# PWR.net
KiCad netlist of a schematic drawn in Altium Designer
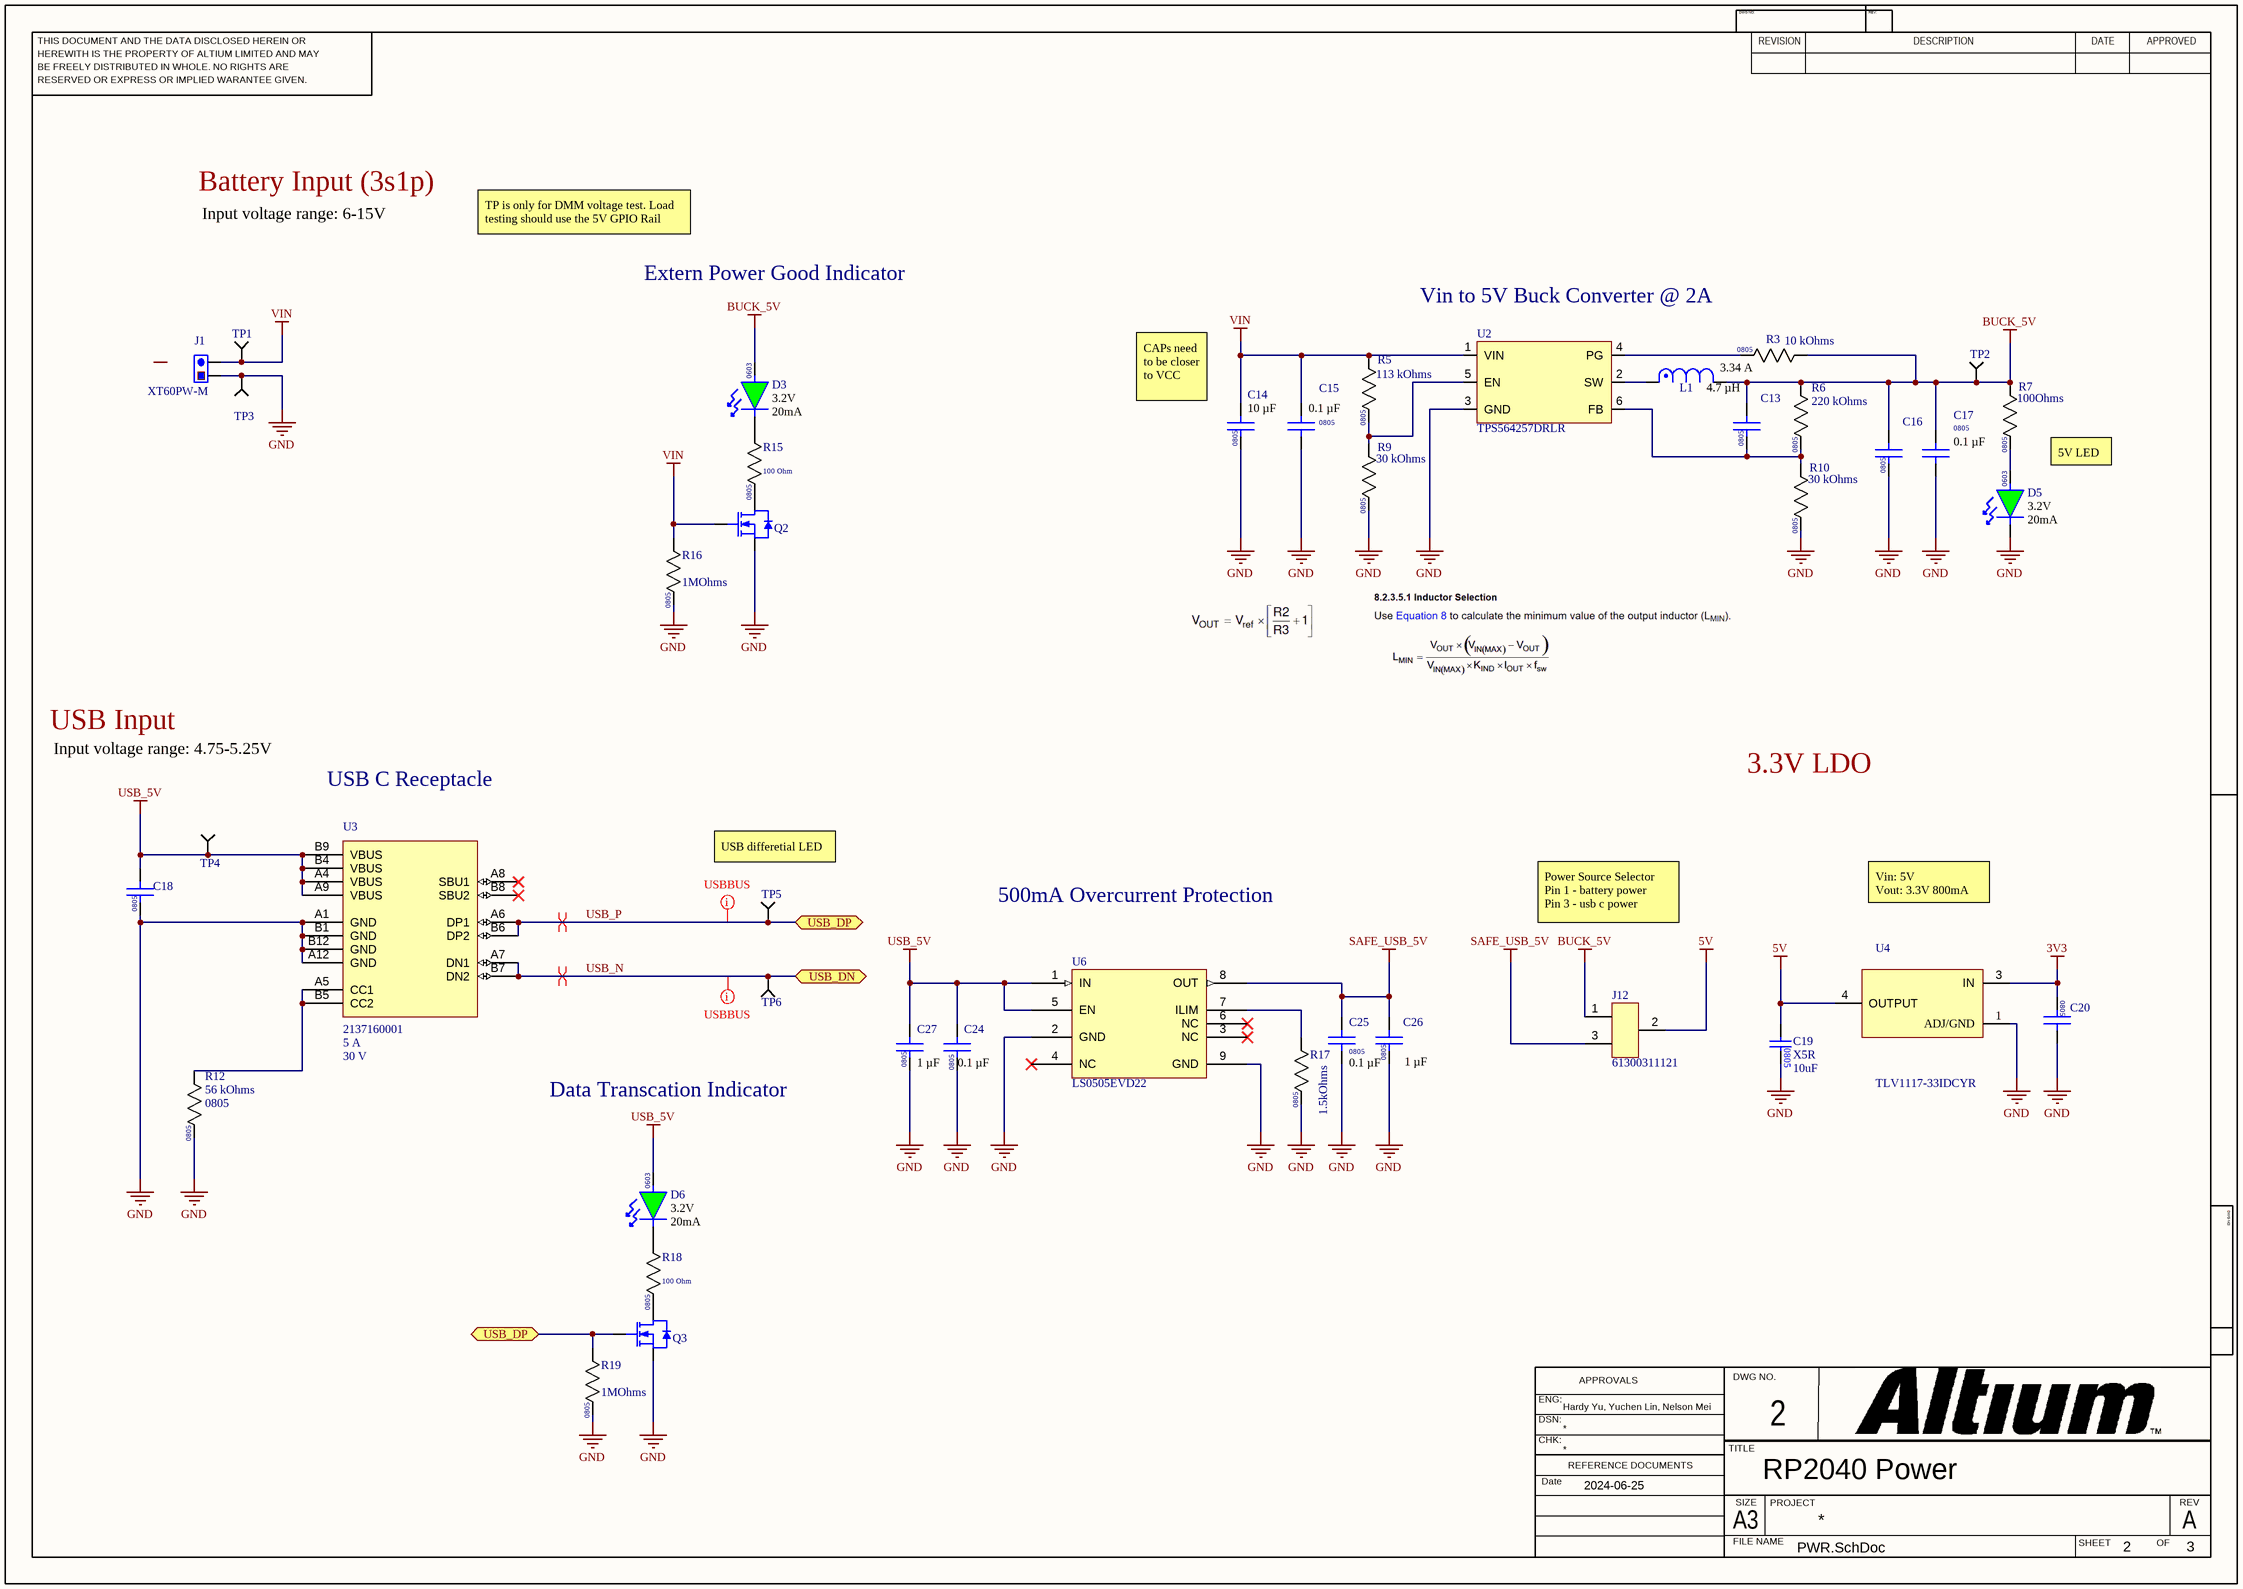
[diagram p0: PWR.SchDoc]

(export (version "E")
  (design (tool "Eeschema 10.0.6"))
  (components
    (comp (ref "C13")
      (value "C0805C300J4HAC7800")
      (footprint "CAP_CL21_SAM")
      (description "30 pF ±5% 16V Ceramic Capacitor X8R 0805 (2012 Metric)")
      (libsource (lib "RP2040_dev_board") (part "C0805C300J4HAC7800"))
    )
    (comp (ref "C14")
      (value "CL21A106KOQNNNE")
      (footprint "CAP_CL21_SAM")
      (description "10 µF ±10% 16V Ceramic Capacitor X5R 0805 (2012 Metric)")
      (fields (field (name "CAPACITANCE") "10 µF"))
      (libsource (lib "RP2040_dev_board") (part "CL21A106KOQNNNE"))
    )
    (comp (ref "C15")
      (value "C0805C104K4RAC7800")
      (footprint "CAP_CL21_SAM")
      (description "0.1 µF ±10% 16V Ceramic Capacitor X7R 0805 (2012 Metric)")
      (fields (field (name "CAPACITANCE") "0.1 µF") (field (name "PACKAGE / CASE") "0805"))
      (libsource (lib "RP2040_dev_board") (part "C0805C104K4RAC7800"))
    )
    (comp (ref "C16")
      (value "CL21A226MOCLRNC")
      (footprint "CAP_CL21_SAM")
      (description "22 µF ±20% 16V Ceramic Capacitor X5R 0805 (2012 Metric)")
      (libsource (lib "RP2040_dev_board") (part "CL21A226MOCLRNC"))
    )
    (comp (ref "C17")
      (value "C0805C104K4RAC7800")
      (footprint "CAP_CL21_SAM")
      (description "0.1 µF ±10% 16V Ceramic Capacitor X7R 0805 (2012 Metric)")
      (fields (field (name "CAPACITANCE") "0.1 µF") (field (name "PACKAGE / CASE") "0805"))
      (libsource (lib "RP2040_dev_board") (part "C0805C104K4RAC7800"))
    )
    (comp (ref "C18")
      (value "CC0805MRX7R9BB103")
      (footprint "CAP_CL21_SAM")
      (description "10000 pF ±20% 50V Ceramic Capacitor X7R 0805 (2012 Metric)")
      (fields (field (name "VOLTAGE") "50V") (field (name "TOLERANCE") "20%"))
      (libsource (lib "RP2040_dev_board") (part "CC0805MRX7R9BB103"))
    )
    (comp (ref "C19")
      (value "10uF")
      (footprint ".CAP_0805-Footprint-1")
      (description "CAP CER 10UF 16V X5R 0805")
      (fields
        (field (name "VOLTAGE") "16V")
        (field (name "TEMPERATURE COEFFICIENT") "X5R")
        (field (name "Comment") "CL21A106KOQNNNE")
      )
      (libsource (lib "WARG") (part ".CAP_0805-Symbol-1"))
    )
    (comp (ref "C20")
      (value "EMK325ABJ107MM-T")
      (footprint "CAP_EMK325AB_3P2X2P5_TAY-L")
      (description "100 µF ±20% 16V Ceramic Capacitor X5R 1210 (3225 Metric)")
      (fields (field (name "TOLERANCE") "20%"))
      (libsource (lib "RP2040_dev_board") (part "EMK325ABJ107MM-T"))
    )
    (comp (ref "C24")
      (value "C0805C104K4RAC7800")
      (footprint "CAP_CL21_SAM")
      (description "0.1 µF ±10% 16V Ceramic Capacitor X7R 0805 (2012 Metric)")
      (fields (field (name "CAPACITANCE") "0.1 µF") (field (name "PACKAGE / CASE") "0805"))
      (libsource (lib "RP2040_dev_board") (part "C0805C104K4RAC7800"))
    )
    (comp (ref "C25")
      (value "C0805C104K4RAC7800")
      (footprint "CAP_CL21_SAM")
      (description "0.1 µF ±10% 16V Ceramic Capacitor X7R 0805 (2012 Metric)")
      (fields (field (name "CAPACITANCE") "0.1 µF") (field (name "PACKAGE / CASE") "0805"))
      (libsource (lib "RP2040_dev_board") (part "C0805C104K4RAC7800"))
    )
    (comp (ref "C26")
      (value "0805B105K250DC")
      (footprint "CAP_CL21_SAM")
      (description "CAP SMD,0805,X7R,1UF,10%,25V")
      (fields (field (name "CAPACITANCE") "1 µF"))
      (libsource (lib "RP2040_dev_board") (part "0805B105K250DC"))
    )
    (comp (ref "C27")
      (value "0805B105K250DC")
      (footprint "CAP_CL21_SAM")
      (description "CAP SMD,0805,X7R,1UF,10%,25V")
      (fields (field (name "CAPACITANCE") "1 µF"))
      (libsource (lib "RP2040_dev_board") (part "0805B105K250DC"))
    )
    (comp (ref "D3")
      (value "150060GS75000")
      (footprint ".LED_0603-Footprint-1")
      (description "Green 520nm LED Indication - Discrete 3.2V 0603 (1608 Metric)")
      (fields (field (name "VOLTAGE - FORWARD (VF) (TYP)") "3.2V") (field (name "CURRENT - TEST") "20mA"))
      (libsource (lib "RP2040_dev_board") (part "150060GS75000"))
    )
    (comp (ref "D5")
      (value "150060GS75000")
      (footprint ".LED_0603-Footprint-1")
      (description "Green 520nm LED Indication - Discrete 3.2V 0603 (1608 Metric)")
      (fields (field (name "VOLTAGE - FORWARD (VF) (TYP)") "3.2V") (field (name "CURRENT - TEST") "20mA"))
      (libsource (lib "RP2040_dev_board") (part "150060GS75000"))
    )
    (comp (ref "D6")
      (value "150060GS75000")
      (footprint ".LED_0603-Footprint-1")
      (description "Green 520nm LED Indication - Discrete 3.2V 0603 (1608 Metric)")
      (fields (field (name "VOLTAGE - FORWARD (VF) (TYP)") "3.2V") (field (name "CURRENT - TEST") "20mA"))
      (libsource (lib "RP2040_dev_board") (part "150060GS75000"))
    )
    (comp (ref "J1")
      (value "XT60PW-M")
      (footprint "AMASS_XT60PW-M")
      (description "Socket, DC supply, male, PIN: 2")
      (fields (field (name "MF") "AMASS"))
      (libsource (lib "RP2040_dev_board") (part "XT60PW-M"))
    )
    (comp (ref "J12")
      (value "61300311121")
      (footprint "61300311121")
      (description "CONN HEADER VERT 3POS 2.54MM")
      (libsource (lib "RP2040_dev_board") (part "61300311121"))
    )
    (comp (ref "L1")
      (value "DR74-4R7-R")
      (footprint "DR74")
      (description "4.7 µH Shielded Drum Core, Wirewound Inductor 3.34 A 25.4mOhm Nonstandard")
      (fields (field (name "REFDES") "4.7 µH") (field (name "CURRENT RATING (AMPS)") "3.34 A"))
      (libsource (lib "RP2040_dev_board") (part "DR74-4R7-R"))
    )
    (comp (ref "Q2")
      (value "DMG2302UKQ-7")
      (footprint ".SOT23-3")
      (description "MOSFET N-CH 20V 2.8A SOT23 T&R 3")
      (libsource (lib "WARG") (part ".NCH"))
    )
    (comp (ref "Q3")
      (value "DMG2302UKQ-7")
      (footprint ".SOT23-3")
      (description "MOSFET N-CH 20V 2.8A SOT23 T&R 3")
      (libsource (lib "WARG") (part ".NCH"))
    )
    (comp (ref "R3")
      (value "ERJ-6GEYJ103V")
      (footprint "RESC1608X50N")
      (description "10 kOhms ±5% 0.125W, 1/8W Chip Resistor 0805 (2012 Metric) Automotive AEC-Q200 Thick Film")
      (fields (field (name "RESISTANCE") "10 kOhms") (field (name "TOLERANCE") "±5%"))
      (libsource (lib "RP2040_dev_board") (part "ERJ-6GEYJ103V"))
    )
    (comp (ref "R5")
      (value "ERJ-6ENF1133V")
      (footprint "RESC1608X50N")
      (description "113 kOhms ±1% 0.125W, 1/8W Chip Resistor 0805 (2012 Metric) Automotive AEC-Q200 Thick Film")
      (fields (field (name "RESISTANCE") "113 kOhms") (field (name "TOLERANCE") "±1%"))
      (libsource (lib "RP2040_dev_board") (part "ERJ-6ENF1133V"))
    )
    (comp (ref "R6")
      (value "CRG0805F220K")
      (footprint "RESC2012X65N")
      (description "220 kOhms ±1% 0.125W, 1/8W Chip Resistor 0805 (2012 Metric) Thick Film")
      (fields (field (name "RESISTANCE") "220 kOhms") (field (name "TOLERANCE") "±1%"))
      (libsource (lib "RP2040_dev_board") (part "CRG0805F220K"))
    )
    (comp (ref "R7")
      (value "RC0603FR-07100RL")
      (footprint "RESC2012X65N")
      (description "100 Ohms ±1% 0.1W, 1/10W Chip Resistor 0603 (1608 Metric) Moisture Resistant Thick Film")
      (fields (field (name "RESISTANCE") "100Ohms") (field (name "TOLERANCE") "±1%"))
      (libsource (lib "RP2040_dev_board") (part "RC0603FR-07100RL"))
    )
    (comp (ref "R9")
      (value "RMCF0805FT30K0")
      (footprint "RESC2012X65N")
      (description "30 kOhms ±1% 0.125W, 1/8W Chip Resistor 0805 (2012 Metric) Automotive AEC-Q200 Thick Film")
      (fields (field (name "RESISTANCE") "30 kOhms") (field (name "TOLERANCE") "±1%"))
      (libsource (lib "RP2040_dev_board") (part "RMCF0805FT30K0"))
    )
    (comp (ref "R10")
      (value "RMCF0805FT30K0")
      (footprint "RESC2012X65N")
      (description "30 kOhms ±1% 0.125W, 1/8W Chip Resistor 0805 (2012 Metric) Automotive AEC-Q200 Thick Film")
      (fields (field (name "RESISTANCE") "30 kOhms") (field (name "TOLERANCE") "±1%"))
      (libsource (lib "RP2040_dev_board") (part "RMCF0805FT30K0"))
    )
    (comp (ref "R12")
      (value "ERJ-6GEYJ563V")
      (footprint "RES_ERJ-6GEYJ563V")
      (description "56 kOhms ±5% 0.125W, 1/8W Chip Resistor 0805 (2012 Metric) Automotive AEC-Q200 Thick Film")
      (fields
        (field (name "RESISTANCE") "56 kOhms")
        (field (name "TOLERANCE") "±5%")
        (field (name "PACKAGE") "0805")
      )
      (libsource (lib "RP2040_dev_board") (part "ERJ-6GEYJ563V"))
    )
    (comp (ref "R15")
      (value "RMCF0805FT100R")
      (footprint ".RES_0805-Footprint-1")
      (description "RES 100 OHM 1% 1/8W 0805")
      (fields (field (name "RESISTENCE") "100 Ohm"))
      (libsource (lib "RP2040_dev_board") (part "RMCF0805FT100R"))
    )
    (comp (ref "R16")
      (value "RC0805FR-071ML")
      (footprint ".RES_0805-Footprint-1")
      (description "RES 1M OHM 1% 1/8W 0805")
      (fields (field (name "POWER") "1/8W") (field (name "RESISTANCE") "1MOhms"))
      (libsource (lib "RP2040_dev_board") (part "RC0805FR-071ML"))
    )
    (comp (ref "R17")
      (value "RC0805FR-071K5L")
      (footprint "RESC2012X65N")
      (description "1.5 kOhms ±1% 0.125W, 1/8W Chip Resistor 0805 (2012 Metric) Moisture Resistant Thick Film")
      (fields (field (name "RESISTANCE") "1.5kOhms") (field (name "TOLERANCE") "±1%"))
      (libsource (lib "RP2040_dev_board") (part "RC0805FR-071K5L"))
    )
    (comp (ref "R18")
      (value "RMCF0805FT100R")
      (footprint ".RES_0805-Footprint-1")
      (description "RES 100 OHM 1% 1/8W 0805")
      (fields (field (name "RESISTENCE") "100 Ohm"))
      (libsource (lib "RP2040_dev_board") (part "RMCF0805FT100R"))
    )
    (comp (ref "R19")
      (value "RC0805FR-071ML")
      (footprint ".RES_0805-Footprint-1")
      (description "RES 1M OHM 1% 1/8W 0805")
      (fields (field (name "POWER") "1/8W") (field (name "RESISTANCE") "1MOhms"))
      (libsource (lib "RP2040_dev_board") (part "RC0805FR-071ML"))
    )
    (comp (ref "TP1")
      (value "5002")
      (footprint "KEYSTONE_5002")
      (fields (field (name "MF") "Keystone Electronics"))
      (libsource (lib "RP2040_dev_board") (part "5002"))
    )
    (comp (ref "TP2")
      (value "5002")
      (footprint "KEYSTONE_5002")
      (fields (field (name "MF") "Keystone Electronics"))
      (libsource (lib "RP2040_dev_board") (part "5002"))
    )
    (comp (ref "TP3")
      (value "5002")
      (footprint "KEYSTONE_5002")
      (fields (field (name "MF") "Keystone Electronics"))
      (libsource (lib "RP2040_dev_board") (part "5002"))
    )
    (comp (ref "TP4")
      (value "5002")
      (footprint "KEYSTONE_5002")
      (fields (field (name "MF") "Keystone Electronics"))
      (libsource (lib "RP2040_dev_board") (part "5002"))
    )
    (comp (ref "TP5")
      (value "5002")
      (footprint "KEYSTONE_5002")
      (fields (field (name "MF") "Keystone Electronics"))
      (libsource (lib "RP2040_dev_board") (part "5002"))
    )
    (comp (ref "TP6")
      (value "5002")
      (footprint "KEYSTONE_5002")
      (fields (field (name "MF") "Keystone Electronics"))
      (libsource (lib "RP2040_dev_board") (part "5002"))
    )
    (comp (ref "U2")
      (value "TPS564257DRLR")
      (footprint "TPS564242DRLR_TEX")
      (description "Buck Switching Regulator IC Positive Adjustable 0.6V 1 Output 4A SOT-563, SOT-666")
      (libsource (lib "RP2040_dev_board") (part "TPS564257DRLR"))
    )
    (comp (ref "U3")
      (value "2137160001")
      (footprint "MOLEX_2137160001")
      (description "CONN RCPT USB2.0 TYPE C 24POS RA")
      (fields (field (name "RATED CURENT") "5 A") (field (name "RATED VOLTAGE") "30 V"))
      (libsource (lib "RP2040_dev_board") (part "2137160001"))
    )
    (comp (ref "U4")
      (value "TLV1117-33IDCYR")
      (footprint "DCY0004A_L")
      (description "800-mA, 15-V, linear voltage regulator, 3.3V fixoutput, Adjustable output")
      (libsource (lib "RP2040_dev_board") (part "TLV1117-33IDCYR"))
    )
    (comp (ref "U6")
      (value "LS0505EVD22")
      (footprint "LS0505EVD22_LTF")
      (description "IC ELECTRONIC FUSE 10DFN")
      (libsource (lib "RP2040_dev_board") (part "LS0505EVD22"))
    )
  )
  (nets
    (net (code "1") (name "/USB_N") (class "Default")
      (node (ref "TP6") (pin "TP") (pinfunction "TP_TP") (pintype "passive"))
      (node (ref "U3") (pin "A7") (pinfunction "DN1_A7") (pintype "bidirectional"))
      (node (ref "U3") (pin "B7") (pinfunction "DN2_B7") (pintype "bidirectional"))
    )
    (net (code "2") (name "/USB_P") (class "Default")
      (node (ref "Q3") (pin "1") (pinfunction "Gate_1") (pintype "passive"))
      (node (ref "R19") (pin "1") (pinfunction "1_1") (pintype "passive"))
      (node (ref "TP5") (pin "TP") (pinfunction "TP_TP") (pintype "passive"))
      (node (ref "U3") (pin "A6") (pinfunction "DP1_A6") (pintype "bidirectional"))
      (node (ref "U3") (pin "B6") (pinfunction "DP2_B6") (pintype "bidirectional"))
    )
    (net (code "3") (name "3V3") (class "Default")
      (node (ref "C20") (pin "1") (pinfunction "1_1") (pintype "passive"))
      (node (ref "U4") (pin "3") (pinfunction "IN_3") (pintype "power_in"))
    )
    (net (code "4") (name "5V") (class "Default")
      (node (ref "C19") (pin "1") (pinfunction "1_1") (pintype "passive"))
      (node (ref "J12") (pin "2") (pinfunction "2_2") (pintype "passive"))
      (node (ref "U4") (pin "4") (pinfunction "OUTPUT_4") (pintype "power_in"))
    )
    (net (code "5") (name "BUCK_5V") (class "Default")
      (node (ref "C13") (pin "2") (pinfunction "2_2") (pintype "passive"))
      (node (ref "C16") (pin "2") (pinfunction "2_2") (pintype "passive"))
      (node (ref "C17") (pin "2") (pinfunction "2_2") (pintype "passive"))
      (node (ref "D3") (pin "2") (pinfunction "+_2") (pintype "passive"))
      (node (ref "J12") (pin "1") (pinfunction "1_1") (pintype "passive"))
      (node (ref "L1") (pin "2") (pinfunction "2_2") (pintype "passive"))
      (node (ref "R3") (pin "1") (pinfunction "1_1") (pintype "passive"))
      (node (ref "R6") (pin "1") (pinfunction "1_1") (pintype "passive"))
      (node (ref "R7") (pin "1") (pinfunction "1_1") (pintype "passive"))
      (node (ref "TP2") (pin "TP") (pinfunction "TP_TP") (pintype "passive"))
    )
    (net (code "6") (name "GND") (class "Default")
      (node (ref "C14") (pin "1") (pinfunction "1_1") (pintype "passive"))
      (node (ref "C15") (pin "1") (pinfunction "1_1") (pintype "passive"))
      (node (ref "C16") (pin "1") (pinfunction "1_1") (pintype "passive"))
      (node (ref "C17") (pin "1") (pinfunction "1_1") (pintype "passive"))
      (node (ref "C18") (pin "1") (pinfunction "1_1") (pintype "passive"))
      (node (ref "C19") (pin "2") (pinfunction "2_2") (pintype "passive"))
      (node (ref "C20") (pin "2") (pinfunction "2_2") (pintype "passive"))
      (node (ref "C24") (pin "1") (pinfunction "1_1") (pintype "passive"))
      (node (ref "C25") (pin "1") (pinfunction "1_1") (pintype "passive"))
      (node (ref "C26") (pin "1") (pinfunction "1_1") (pintype "passive"))
      (node (ref "C27") (pin "1") (pinfunction "1_1") (pintype "passive"))
      (node (ref "D5") (pin "1") (pinfunction "-_1") (pintype "passive"))
      (node (ref "J1") (pin "1") (pinfunction "POS_1") (pintype "passive"))
      (node (ref "Q2") (pin "2") (pinfunction "Source_2") (pintype "passive"))
      (node (ref "Q3") (pin "2") (pinfunction "Source_2") (pintype "passive"))
      (node (ref "R10") (pin "2") (pinfunction "2_2") (pintype "passive"))
      (node (ref "R12") (pin "2") (pinfunction "2_2") (pintype "passive"))
      (node (ref "R16") (pin "2") (pinfunction "2_2") (pintype "passive"))
      (node (ref "R17") (pin "2") (pinfunction "2_2") (pintype "passive"))
      (node (ref "R19") (pin "2") (pinfunction "2_2") (pintype "passive"))
      (node (ref "R9") (pin "2") (pinfunction "2_2") (pintype "passive"))
      (node (ref "TP3") (pin "TP") (pinfunction "TP_TP") (pintype "passive"))
      (node (ref "U2") (pin "3") (pinfunction "GND_3") (pintype "passive"))
      (node (ref "U3") (pin "A1") (pinfunction "GND_A1") (pintype "power_in"))
      (node (ref "U3") (pin "A12") (pinfunction "GND_A12") (pintype "power_in"))
      (node (ref "U3") (pin "B1") (pinfunction "GND_B1") (pintype "power_in"))
      (node (ref "U3") (pin "B12") (pinfunction "GND_B12") (pintype "power_in"))
      (node (ref "U4") (pin "1") (pinfunction "ADJ/GND_1") (pintype "power_in"))
      (node (ref "U6") (pin "2") (pinfunction "GND_2") (pintype "power_in"))
      (node (ref "U6") (pin "9") (pinfunction "GND_9") (pintype "power_in"))
    )
    (net (code "7") (name "Net-(D3--)") (class "Default")
      (node (ref "D3") (pin "1") (pinfunction "-_1") (pintype "passive"))
      (node (ref "R15") (pin "1") (pinfunction "1_1") (pintype "passive"))
    )
    (net (code "8") (name "Net-(D5-+)") (class "Default")
      (node (ref "D5") (pin "2") (pinfunction "+_2") (pintype "passive"))
      (node (ref "R7") (pin "2") (pinfunction "2_2") (pintype "passive"))
    )
    (net (code "9") (name "Net-(D6--)") (class "Default")
      (node (ref "D6") (pin "1") (pinfunction "-_1") (pintype "passive"))
      (node (ref "R18") (pin "1") (pinfunction "1_1") (pintype "passive"))
    )
    (net (code "10") (name "Net-(Q2-Drain)") (class "Default")
      (node (ref "Q2") (pin "3") (pinfunction "Drain_3") (pintype "passive"))
      (node (ref "R15") (pin "2") (pinfunction "2_2") (pintype "passive"))
    )
    (net (code "11") (name "Net-(Q3-Drain)") (class "Default")
      (node (ref "Q3") (pin "3") (pinfunction "Drain_3") (pintype "passive"))
      (node (ref "R18") (pin "2") (pinfunction "2_2") (pintype "passive"))
    )
    (net (code "12") (name "Net-(U2-EN)") (class "Default")
      (node (ref "R5") (pin "2") (pinfunction "2_2") (pintype "passive"))
      (node (ref "R9") (pin "1") (pinfunction "1_1") (pintype "passive"))
      (node (ref "U2") (pin "5") (pinfunction "EN_5") (pintype "passive"))
    )
    (net (code "13") (name "Net-(U2-FB)") (class "Default")
      (node (ref "C13") (pin "1") (pinfunction "1_1") (pintype "passive"))
      (node (ref "R10") (pin "1") (pinfunction "1_1") (pintype "passive"))
      (node (ref "R6") (pin "2") (pinfunction "2_2") (pintype "passive"))
      (node (ref "U2") (pin "6") (pinfunction "FB_6") (pintype "passive"))
    )
    (net (code "14") (name "Net-(U2-PG)") (class "Default")
      (node (ref "R3") (pin "2") (pinfunction "2_2") (pintype "passive"))
      (node (ref "U2") (pin "4") (pinfunction "PG_4") (pintype "passive"))
    )
    (net (code "15") (name "Net-(U2-SW)") (class "Default")
      (node (ref "L1") (pin "1") (pinfunction "1_1") (pintype "passive"))
      (node (ref "U2") (pin "2") (pinfunction "SW_2") (pintype "passive"))
    )
    (net (code "16") (name "Net-(U3-CC1)") (class "Default")
      (node (ref "R12") (pin "1") (pinfunction "1_1") (pintype "passive"))
      (node (ref "U3") (pin "A5") (pinfunction "CC1_A5") (pintype "passive"))
      (node (ref "U3") (pin "B5") (pinfunction "CC2_B5") (pintype "passive"))
    )
    (net (code "17") (name "Net-(U6-ILIM)") (class "Default")
      (node (ref "R17") (pin "1") (pinfunction "1_1") (pintype "passive"))
      (node (ref "U6") (pin "7") (pinfunction "ILIM_7") (pintype "passive"))
    )
    (net (code "18") (name "SAFE_USB_5V") (class "Default")
      (node (ref "C25") (pin "2") (pinfunction "2_2") (pintype "passive"))
      (node (ref "C26") (pin "2") (pinfunction "2_2") (pintype "passive"))
      (node (ref "J12") (pin "3") (pinfunction "3_3") (pintype "passive"))
      (node (ref "U6") (pin "8") (pinfunction "OUT_8") (pintype "output"))
    )
    (net (code "19") (name "USB_5V") (class "Default")
      (node (ref "C18") (pin "2") (pinfunction "2_2") (pintype "passive"))
      (node (ref "C24") (pin "2") (pinfunction "2_2") (pintype "passive"))
      (node (ref "C27") (pin "2") (pinfunction "2_2") (pintype "passive"))
      (node (ref "D6") (pin "2") (pinfunction "+_2") (pintype "passive"))
      (node (ref "TP4") (pin "TP") (pinfunction "TP_TP") (pintype "passive"))
      (node (ref "U3") (pin "A4") (pinfunction "VBUS_A4") (pintype "power_in"))
      (node (ref "U3") (pin "A9") (pinfunction "VBUS_A9") (pintype "power_in"))
      (node (ref "U3") (pin "B4") (pinfunction "VBUS_B4") (pintype "power_in"))
      (node (ref "U3") (pin "B9") (pinfunction "VBUS_B9") (pintype "power_in"))
      (node (ref "U6") (pin "1") (pinfunction "IN_1") (pintype "input"))
      (node (ref "U6") (pin "5") (pinfunction "EN_5") (pintype "passive"))
    )
    (net (code "20") (name "VIN") (class "Default")
      (node (ref "C14") (pin "2") (pinfunction "2_2") (pintype "passive"))
      (node (ref "C15") (pin "2") (pinfunction "2_2") (pintype "passive"))
      (node (ref "J1") (pin "2") (pinfunction "NEG_2") (pintype "passive"))
      (node (ref "Q2") (pin "1") (pinfunction "Gate_1") (pintype "passive"))
      (node (ref "R16") (pin "1") (pinfunction "1_1") (pintype "passive"))
      (node (ref "R5") (pin "1") (pinfunction "1_1") (pintype "passive"))
      (node (ref "TP1") (pin "TP") (pinfunction "TP_TP") (pintype "passive"))
      (node (ref "U2") (pin "1") (pinfunction "VIN_1") (pintype "passive"))
    )
    (net (code "21") (name "unconnected-(U3-SBU1-PadA8)") (class "Default")
      (node (ref "U3") (pin "A8") (pinfunction "SBU1_A8") (pintype "bidirectional+no_connect"))
    )
    (net (code "22") (name "unconnected-(U3-SBU2-PadB8)") (class "Default")
      (node (ref "U3") (pin "B8") (pinfunction "SBU2_B8") (pintype "bidirectional+no_connect"))
    )
    (net (code "23") (name "unconnected-(U6-NC-Pad3)") (class "Default")
      (node (ref "U6") (pin "3") (pinfunction "NC_3") (pintype "passive+no_connect"))
    )
    (net (code "24") (name "unconnected-(U6-NC-Pad4)") (class "Default")
      (node (ref "U6") (pin "4") (pinfunction "NC_4") (pintype "passive+no_connect"))
    )
    (net (code "25") (name "unconnected-(U6-NC-Pad6)") (class "Default")
      (node (ref "U6") (pin "6") (pinfunction "NC_6") (pintype "passive+no_connect"))
    )
  )
)
